# v3pow_1_4v7.net
KiCad netlist of a schematic drawn in EAGLE
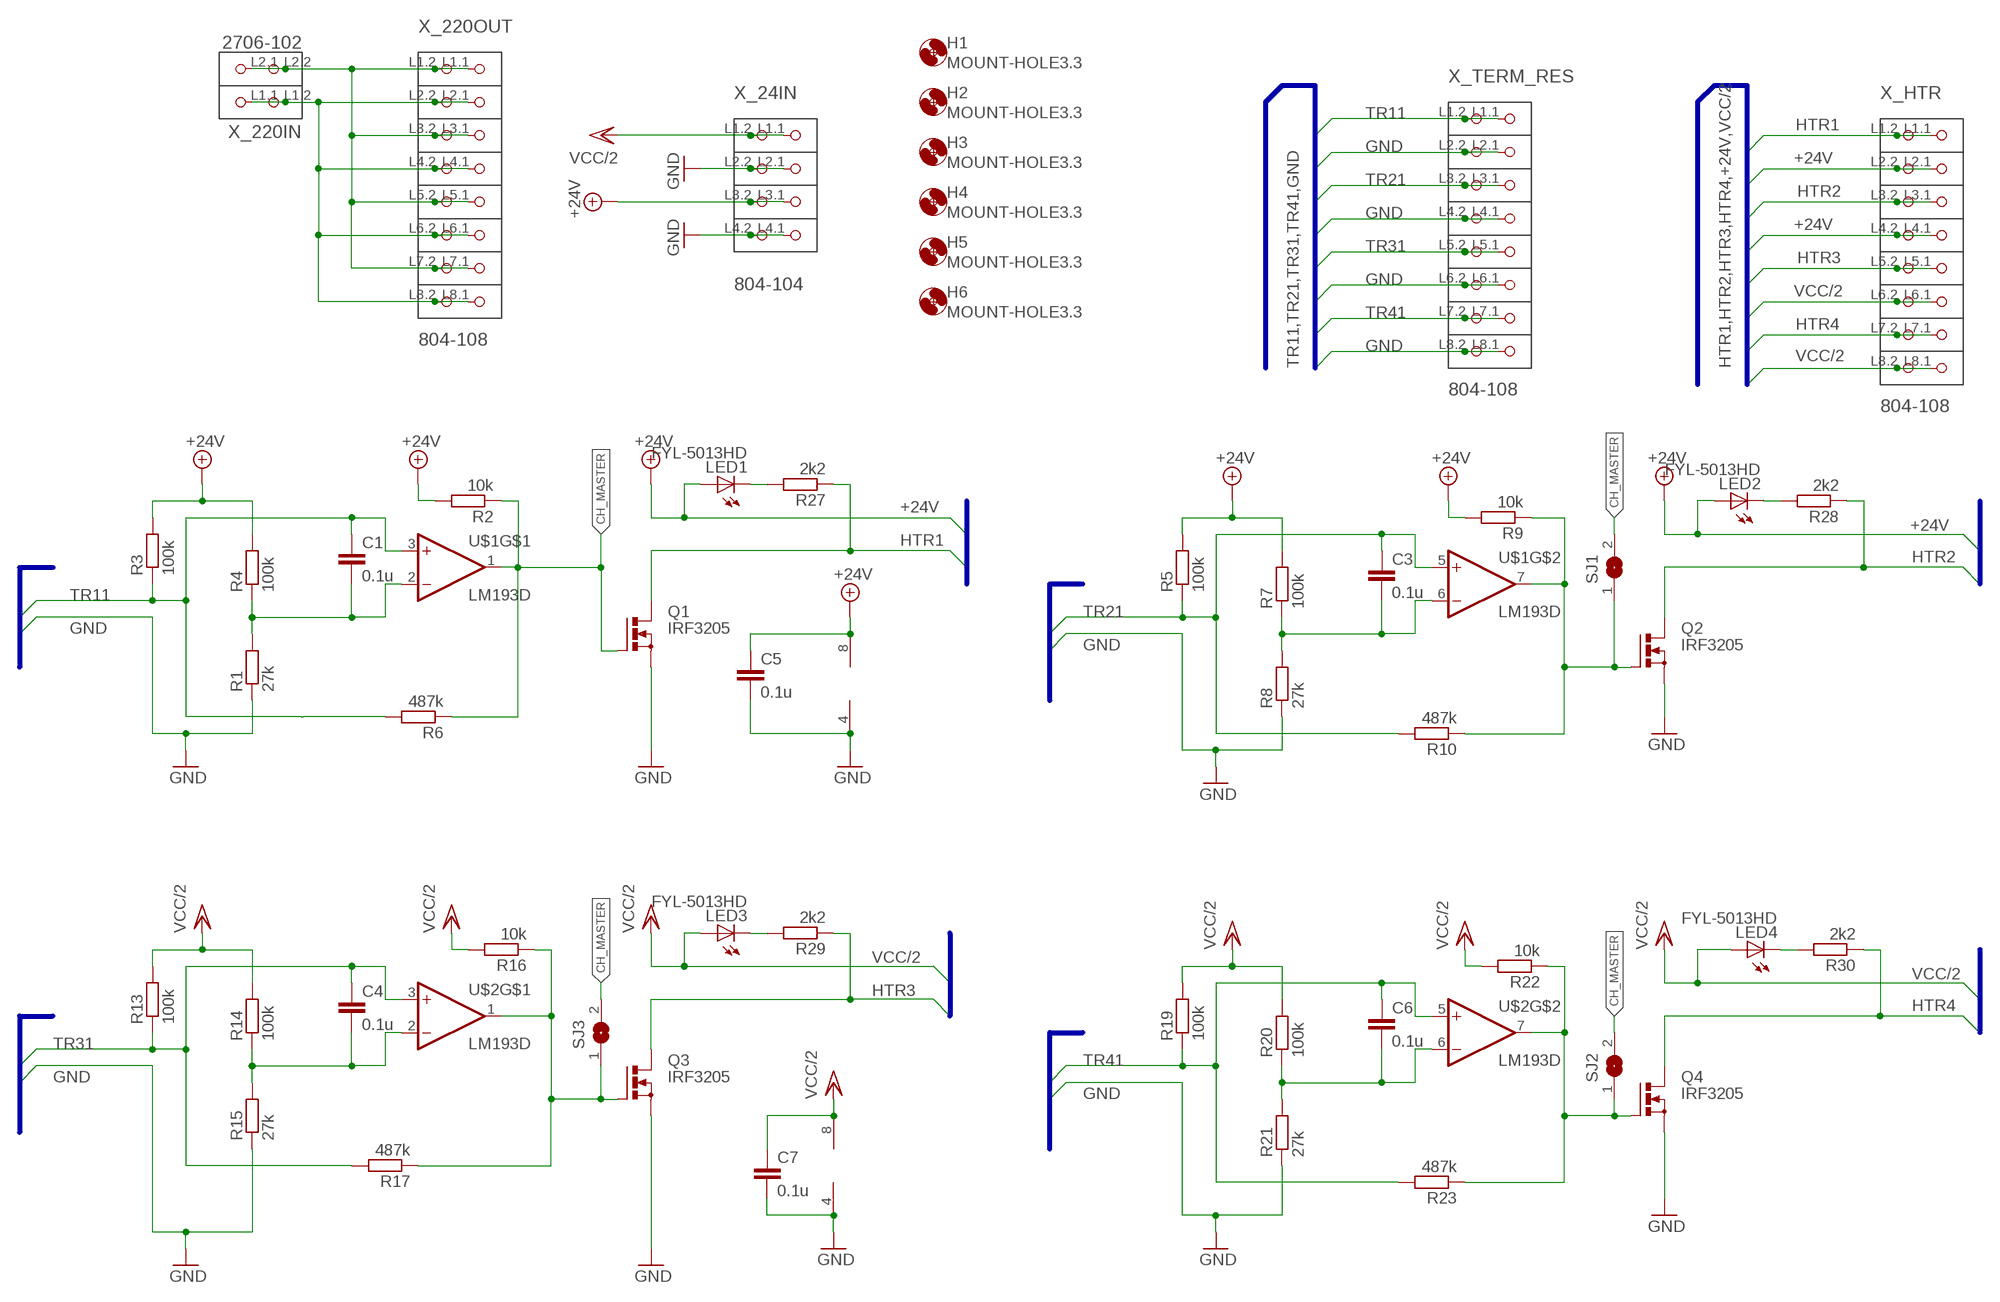
[diagram p0: schematic, sheet 1]

(export (version "E")
  (design (tool "Eeschema 10.0.6"))
  (components
    (comp (ref "C1")
      (value "0.1u")
      (footprint "eagle-import:C0805")
      (libsource (lib "eagle-import") (part "C-EUC0805"))
    )
    (comp (ref "C3")
      (value "0.1u")
      (footprint "eagle-import:C0805")
      (libsource (lib "eagle-import") (part "C-EUC0805"))
    )
    (comp (ref "C4")
      (value "0.1u")
      (footprint "eagle-import:C0805")
      (libsource (lib "eagle-import") (part "C-EUC0805"))
    )
    (comp (ref "C5")
      (value "0.1u")
      (footprint "eagle-import:C0805")
      (libsource (lib "eagle-import") (part "C-EUC0805"))
    )
    (comp (ref "C6")
      (value "0.1u")
      (footprint "eagle-import:C0805")
      (libsource (lib "eagle-import") (part "C-EUC0805"))
    )
    (comp (ref "C7")
      (value "0.1u")
      (footprint "eagle-import:C0805")
      (libsource (lib "eagle-import") (part "C-EUC0805"))
    )
    (comp (ref "H1")
      (value "MOUNT-HOLE3.3")
      (footprint "eagle-import:3,3")
      (libsource (lib "eagle-import") (part "MOUNT-HOLE3.3"))
    )
    (comp (ref "H2")
      (value "MOUNT-HOLE3.3")
      (footprint "eagle-import:3,3")
      (libsource (lib "eagle-import") (part "MOUNT-HOLE3.3"))
    )
    (comp (ref "H3")
      (value "MOUNT-HOLE3.3")
      (footprint "eagle-import:3,3")
      (libsource (lib "eagle-import") (part "MOUNT-HOLE3.3"))
    )
    (comp (ref "H4")
      (value "MOUNT-HOLE3.3")
      (footprint "eagle-import:3,3")
      (libsource (lib "eagle-import") (part "MOUNT-HOLE3.3"))
    )
    (comp (ref "H5")
      (value "MOUNT-HOLE3.3")
      (footprint "eagle-import:3,3")
      (libsource (lib "eagle-import") (part "MOUNT-HOLE3.3"))
    )
    (comp (ref "H6")
      (value "MOUNT-HOLE3.3")
      (footprint "eagle-import:3,3")
      (libsource (lib "eagle-import") (part "MOUNT-HOLE3.3"))
    )
    (comp (ref "LED1")
      (value "FYL-5013HD")
      (footprint "eagle-import:LED5MM")
      (libsource (lib "eagle-import") (part "LED5MM"))
    )
    (comp (ref "LED2")
      (value "FYL-5013HD")
      (footprint "eagle-import:LED5MM")
      (libsource (lib "eagle-import") (part "LED5MM"))
    )
    (comp (ref "LED3")
      (value "FYL-5013HD")
      (footprint "eagle-import:LED5MM")
      (libsource (lib "eagle-import") (part "LED5MM"))
    )
    (comp (ref "LED4")
      (value "FYL-5013HD")
      (footprint "eagle-import:LED5MM")
      (libsource (lib "eagle-import") (part "LED5MM"))
    )
    (comp (ref "Q1")
      (value "IRF3205")
      (footprint "eagle-import:TO220BV")
      (libsource (lib "eagle-import") (part "PMOSFET_NTO220BV"))
    )
    (comp (ref "Q2")
      (value "IRF3205")
      (footprint "eagle-import:TO220BV")
      (libsource (lib "eagle-import") (part "PMOSFET_NTO220BV"))
    )
    (comp (ref "Q3")
      (value "IRF3205")
      (footprint "eagle-import:TO220BV")
      (libsource (lib "eagle-import") (part "PMOSFET_NTO220BV"))
    )
    (comp (ref "Q4")
      (value "IRF3205")
      (footprint "eagle-import:TO220BV")
      (libsource (lib "eagle-import") (part "PMOSFET_NTO220BV"))
    )
    (comp (ref "R1")
      (value "27k")
      (footprint "eagle-import:M0805")
      (libsource (lib "eagle-import") (part "R-EU_M0805"))
    )
    (comp (ref "R2")
      (value "10k")
      (footprint "eagle-import:M0805")
      (libsource (lib "eagle-import") (part "R-EU_M0805"))
    )
    (comp (ref "R3")
      (value "100k")
      (footprint "eagle-import:M0805")
      (libsource (lib "eagle-import") (part "R-EU_M0805"))
    )
    (comp (ref "R4")
      (value "100k")
      (footprint "eagle-import:M0805")
      (libsource (lib "eagle-import") (part "R-EU_M0805"))
    )
    (comp (ref "R5")
      (value "100k")
      (footprint "eagle-import:M0805")
      (libsource (lib "eagle-import") (part "R-EU_M0805"))
    )
    (comp (ref "R6")
      (value "487k")
      (footprint "eagle-import:M0805")
      (libsource (lib "eagle-import") (part "R-EU_M0805"))
    )
    (comp (ref "R7")
      (value "100k")
      (footprint "eagle-import:M0805")
      (libsource (lib "eagle-import") (part "R-EU_M0805"))
    )
    (comp (ref "R8")
      (value "27k")
      (footprint "eagle-import:M0805")
      (libsource (lib "eagle-import") (part "R-EU_M0805"))
    )
    (comp (ref "R9")
      (value "10k")
      (footprint "eagle-import:M0805")
      (libsource (lib "eagle-import") (part "R-EU_M0805"))
    )
    (comp (ref "R10")
      (value "487k")
      (footprint "eagle-import:M0805")
      (libsource (lib "eagle-import") (part "R-EU_M0805"))
    )
    (comp (ref "R13")
      (value "100k")
      (footprint "eagle-import:M0805")
      (libsource (lib "eagle-import") (part "R-EU_M0805"))
    )
    (comp (ref "R14")
      (value "100k")
      (footprint "eagle-import:M0805")
      (libsource (lib "eagle-import") (part "R-EU_M0805"))
    )
    (comp (ref "R15")
      (value "27k")
      (footprint "eagle-import:M0805")
      (libsource (lib "eagle-import") (part "R-EU_M0805"))
    )
    (comp (ref "R16")
      (value "10k")
      (footprint "eagle-import:M0805")
      (libsource (lib "eagle-import") (part "R-EU_M0805"))
    )
    (comp (ref "R17")
      (value "487k")
      (footprint "eagle-import:M0805")
      (libsource (lib "eagle-import") (part "R-EU_M0805"))
    )
    (comp (ref "R19")
      (value "100k")
      (footprint "eagle-import:M0805")
      (libsource (lib "eagle-import") (part "R-EU_M0805"))
    )
    (comp (ref "R20")
      (value "100k")
      (footprint "eagle-import:M0805")
      (libsource (lib "eagle-import") (part "R-EU_M0805"))
    )
    (comp (ref "R21")
      (value "27k")
      (footprint "eagle-import:M0805")
      (libsource (lib "eagle-import") (part "R-EU_M0805"))
    )
    (comp (ref "R22")
      (value "10k")
      (footprint "eagle-import:M0805")
      (libsource (lib "eagle-import") (part "R-EU_M0805"))
    )
    (comp (ref "R23")
      (value "487k")
      (footprint "eagle-import:M0805")
      (libsource (lib "eagle-import") (part "R-EU_M0805"))
    )
    (comp (ref "R27")
      (value "2k2")
      (footprint "eagle-import:M0805")
      (libsource (lib "eagle-import") (part "R-EU_M0805"))
    )
    (comp (ref "R28")
      (value "2k2")
      (footprint "eagle-import:M0805")
      (libsource (lib "eagle-import") (part "R-EU_M0805"))
    )
    (comp (ref "R29")
      (value "2k2")
      (footprint "eagle-import:M0805")
      (libsource (lib "eagle-import") (part "R-EU_M0805"))
    )
    (comp (ref "R30")
      (value "2k2")
      (footprint "eagle-import:M0805")
      (libsource (lib "eagle-import") (part "R-EU_M0805"))
    )
    (comp (ref "SJ1") (value "SJ") (footprint "eagle-import:SJ") (libsource (lib "eagle-import") (part "SJ")))
    (comp (ref "SJ2") (value "SJ") (footprint "eagle-import:SJ") (libsource (lib "eagle-import") (part "SJ")))
    (comp (ref "SJ3") (value "SJ") (footprint "eagle-import:SJ") (libsource (lib "eagle-import") (part "SJ")))
    (comp (ref "U$1")
      (value "LM193D")
      (footprint "eagle-import:SO08")
      (libsource (lib "eagle-import") (part "LM193D"))
    )
    (comp (ref "U$2")
      (value "LM193D")
      (footprint "eagle-import:SO08")
      (libsource (lib "eagle-import") (part "LM193D"))
    )
    (comp (ref "X_24IN")
      (value "804-104")
      (footprint "eagle-import:P-804-104")
      (libsource (lib "eagle-import") (part "804-104"))
    )
    (comp (ref "X_220IN")
      (value "2706-102")
      (footprint "eagle-import:P-2706-102")
      (libsource (lib "eagle-import") (part "2706-102"))
    )
    (comp (ref "X_220OUT")
      (value "804-108")
      (footprint "eagle-import:P-804-108")
      (libsource (lib "eagle-import") (part "804-108"))
    )
    (comp (ref "X_HTR")
      (value "804-108")
      (footprint "eagle-import:P-804-108")
      (libsource (lib "eagle-import") (part "804-108"))
    )
    (comp (ref "X_TERM_RES")
      (value "804-108")
      (footprint "eagle-import:P-804-108")
      (libsource (lib "eagle-import") (part "804-108"))
    )
  )
  (nets
    (net (code "5") (name "+24V") (class "Default")
      (node (ref "C5") (pin "1") (pinfunction "1_1") (pintype "passive"))
      (node (ref "LED1") (pin "A") (pinfunction "A_A") (pintype "passive"))
      (node (ref "LED2") (pin "A") (pinfunction "A_A") (pintype "passive"))
      (node (ref "R2") (pin "2") (pinfunction "2_2") (pintype "passive"))
      (node (ref "R3") (pin "2") (pinfunction "2_2") (pintype "passive"))
      (node (ref "R4") (pin "2") (pinfunction "2_2") (pintype "passive"))
      (node (ref "R5") (pin "2") (pinfunction "2_2") (pintype "passive"))
      (node (ref "R7") (pin "2") (pinfunction "2_2") (pintype "passive"))
      (node (ref "R9") (pin "2") (pinfunction "2_2") (pintype "passive"))
      (node (ref "U$1") (pin "8") (pinfunction "V+_8") (pintype "power_in"))
      (node (ref "X_24IN") (pin "L3.1") (pinfunction "P3.1_L3.1") (pintype "bidirectional"))
      (node (ref "X_24IN") (pin "L3.2") (pinfunction "P3.2_L3.2") (pintype "bidirectional"))
      (node (ref "X_HTR") (pin "L2.1") (pinfunction "P2.1_L2.1") (pintype "bidirectional"))
      (node (ref "X_HTR") (pin "L2.2") (pinfunction "P2.2_L2.2") (pintype "bidirectional"))
      (node (ref "X_HTR") (pin "L4.1") (pinfunction "P4.1_L4.1") (pintype "bidirectional"))
      (node (ref "X_HTR") (pin "L4.2") (pinfunction "P4.2_L4.2") (pintype "bidirectional"))
    )
    (net (code "6") (name "/HTR1") (class "Default")
      (node (ref "Q1") (pin "D") (pinfunction "D_D") (pintype "passive"))
      (node (ref "R27") (pin "1") (pinfunction "1_1") (pintype "passive"))
      (node (ref "X_HTR") (pin "L1.1") (pinfunction "P1.1_L1.1") (pintype "bidirectional"))
      (node (ref "X_HTR") (pin "L1.2") (pinfunction "P1.2_L1.2") (pintype "bidirectional"))
    )
    (net (code "7") (name "/HTR2") (class "Default")
      (node (ref "Q2") (pin "D") (pinfunction "D_D") (pintype "passive"))
      (node (ref "R28") (pin "1") (pinfunction "1_1") (pintype "passive"))
      (node (ref "X_HTR") (pin "L3.1") (pinfunction "P3.1_L3.1") (pintype "bidirectional"))
      (node (ref "X_HTR") (pin "L3.2") (pinfunction "P3.2_L3.2") (pintype "bidirectional"))
    )
    (net (code "8") (name "/HTR3") (class "Default")
      (node (ref "Q3") (pin "D") (pinfunction "D_D") (pintype "passive"))
      (node (ref "R29") (pin "1") (pinfunction "1_1") (pintype "passive"))
      (node (ref "X_HTR") (pin "L5.1") (pinfunction "P5.1_L5.1") (pintype "bidirectional"))
      (node (ref "X_HTR") (pin "L5.2") (pinfunction "P5.2_L5.2") (pintype "bidirectional"))
    )
    (net (code "9") (name "/HTR4") (class "Default")
      (node (ref "Q4") (pin "D") (pinfunction "D_D") (pintype "passive"))
      (node (ref "R30") (pin "1") (pinfunction "1_1") (pintype "passive"))
      (node (ref "X_HTR") (pin "L7.1") (pinfunction "P7.1_L7.1") (pintype "bidirectional"))
      (node (ref "X_HTR") (pin "L7.2") (pinfunction "P7.2_L7.2") (pintype "bidirectional"))
    )
    (net (code "10") (name "/TR11") (class "Default")
      (node (ref "C1") (pin "1") (pinfunction "1_1") (pintype "passive"))
      (node (ref "R3") (pin "1") (pinfunction "1_1") (pintype "passive"))
      (node (ref "R6") (pin "2") (pinfunction "2_2") (pintype "passive"))
      (node (ref "U$1") (pin "3") (pinfunction "+IN_3") (pintype "input"))
      (node (ref "X_TERM_RES") (pin "L1.1") (pinfunction "P1.1_L1.1") (pintype "bidirectional"))
      (node (ref "X_TERM_RES") (pin "L1.2") (pinfunction "P1.2_L1.2") (pintype "bidirectional"))
    )
    (net (code "11") (name "/TR21") (class "Default")
      (node (ref "C3") (pin "1") (pinfunction "1_1") (pintype "passive"))
      (node (ref "R10") (pin "2") (pinfunction "2_2") (pintype "passive"))
      (node (ref "R5") (pin "1") (pinfunction "1_1") (pintype "passive"))
      (node (ref "U$1") (pin "5") (pinfunction "+IN_5") (pintype "input"))
      (node (ref "X_TERM_RES") (pin "L3.1") (pinfunction "P3.1_L3.1") (pintype "bidirectional"))
      (node (ref "X_TERM_RES") (pin "L3.2") (pinfunction "P3.2_L3.2") (pintype "bidirectional"))
    )
    (net (code "12") (name "/TR31") (class "Default")
      (node (ref "C4") (pin "1") (pinfunction "1_1") (pintype "passive"))
      (node (ref "R13") (pin "1") (pinfunction "1_1") (pintype "passive"))
      (node (ref "R17") (pin "2") (pinfunction "2_2") (pintype "passive"))
      (node (ref "U$2") (pin "3") (pinfunction "+IN_3") (pintype "input"))
      (node (ref "X_TERM_RES") (pin "L5.1") (pinfunction "P5.1_L5.1") (pintype "bidirectional"))
      (node (ref "X_TERM_RES") (pin "L5.2") (pinfunction "P5.2_L5.2") (pintype "bidirectional"))
    )
    (net (code "13") (name "/TR41") (class "Default")
      (node (ref "C6") (pin "1") (pinfunction "1_1") (pintype "passive"))
      (node (ref "R19") (pin "1") (pinfunction "1_1") (pintype "passive"))
      (node (ref "R23") (pin "2") (pinfunction "2_2") (pintype "passive"))
      (node (ref "U$2") (pin "5") (pinfunction "+IN_5") (pintype "input"))
      (node (ref "X_TERM_RES") (pin "L7.1") (pinfunction "P7.1_L7.1") (pintype "bidirectional"))
      (node (ref "X_TERM_RES") (pin "L7.2") (pinfunction "P7.2_L7.2") (pintype "bidirectional"))
    )
    (net (code "17") (name "CH_MASTER") (class "Default")
      (node (ref "Q1") (pin "G") (pinfunction "G_G") (pintype "passive"))
      (node (ref "R2") (pin "1") (pinfunction "1_1") (pintype "passive"))
      (node (ref "R6") (pin "1") (pinfunction "1_1") (pintype "passive"))
      (node (ref "SJ1") (pin "2") (pinfunction "2_2") (pintype "passive"))
      (node (ref "SJ2") (pin "2") (pinfunction "2_2") (pintype "passive"))
      (node (ref "SJ3") (pin "2") (pinfunction "2_2") (pintype "passive"))
      (node (ref "U$1") (pin "1") (pinfunction "OUT_1") (pintype "output"))
    )
    (net (code "18") (name "GND") (class "Default")
      (node (ref "C5") (pin "2") (pinfunction "2_2") (pintype "passive"))
      (node (ref "C7") (pin "2") (pinfunction "2_2") (pintype "passive"))
      (node (ref "Q1") (pin "S") (pinfunction "S_S") (pintype "passive"))
      (node (ref "Q2") (pin "S") (pinfunction "S_S") (pintype "passive"))
      (node (ref "Q3") (pin "S") (pinfunction "S_S") (pintype "passive"))
      (node (ref "Q4") (pin "S") (pinfunction "S_S") (pintype "passive"))
      (node (ref "R1") (pin "1") (pinfunction "1_1") (pintype "passive"))
      (node (ref "R15") (pin "1") (pinfunction "1_1") (pintype "passive"))
      (node (ref "R21") (pin "1") (pinfunction "1_1") (pintype "passive"))
      (node (ref "R8") (pin "1") (pinfunction "1_1") (pintype "passive"))
      (node (ref "U$1") (pin "4") (pinfunction "V-_4") (pintype "power_in"))
      (node (ref "U$2") (pin "4") (pinfunction "V-_4") (pintype "power_in"))
      (node (ref "X_24IN") (pin "L2.1") (pinfunction "P2.1_L2.1") (pintype "bidirectional"))
      (node (ref "X_24IN") (pin "L2.2") (pinfunction "P2.2_L2.2") (pintype "bidirectional"))
      (node (ref "X_24IN") (pin "L4.1") (pinfunction "P4.1_L4.1") (pintype "bidirectional"))
      (node (ref "X_24IN") (pin "L4.2") (pinfunction "P4.2_L4.2") (pintype "bidirectional"))
      (node (ref "X_TERM_RES") (pin "L2.1") (pinfunction "P2.1_L2.1") (pintype "bidirectional"))
      (node (ref "X_TERM_RES") (pin "L2.2") (pinfunction "P2.2_L2.2") (pintype "bidirectional"))
      (node (ref "X_TERM_RES") (pin "L4.1") (pinfunction "P4.1_L4.1") (pintype "bidirectional"))
      (node (ref "X_TERM_RES") (pin "L4.2") (pinfunction "P4.2_L4.2") (pintype "bidirectional"))
      (node (ref "X_TERM_RES") (pin "L6.1") (pinfunction "P6.1_L6.1") (pintype "bidirectional"))
      (node (ref "X_TERM_RES") (pin "L6.2") (pinfunction "P6.2_L6.2") (pintype "bidirectional"))
      (node (ref "X_TERM_RES") (pin "L8.1") (pinfunction "P8.1_L8.1") (pintype "bidirectional"))
      (node (ref "X_TERM_RES") (pin "L8.2") (pinfunction "P8.2_L8.2") (pintype "bidirectional"))
    )
    (net (code "19") (name "Net-(LED1-C)") (class "Default")
      (node (ref "LED1") (pin "K") (pinfunction "C_K") (pintype "passive"))
      (node (ref "R27") (pin "2") (pinfunction "2_2") (pintype "passive"))
    )
    (net (code "20") (name "Net-(LED2-C)") (class "Default")
      (node (ref "LED2") (pin "K") (pinfunction "C_K") (pintype "passive"))
      (node (ref "R28") (pin "2") (pinfunction "2_2") (pintype "passive"))
    )
    (net (code "21") (name "Net-(LED3-C)") (class "Default")
      (node (ref "LED3") (pin "K") (pinfunction "C_K") (pintype "passive"))
      (node (ref "R29") (pin "2") (pinfunction "2_2") (pintype "passive"))
    )
    (net (code "22") (name "Net-(LED4-C)") (class "Default")
      (node (ref "LED4") (pin "K") (pinfunction "C_K") (pintype "passive"))
      (node (ref "R30") (pin "2") (pinfunction "2_2") (pintype "passive"))
    )
    (net (code "23") (name "Net-(U$1A--IN)") (class "Default")
      (node (ref "C1") (pin "2") (pinfunction "2_2") (pintype "passive"))
      (node (ref "R1") (pin "2") (pinfunction "2_2") (pintype "passive"))
      (node (ref "R4") (pin "1") (pinfunction "1_1") (pintype "passive"))
      (node (ref "U$1") (pin "2") (pinfunction "-IN_2") (pintype "input"))
    )
    (net (code "24") (name "Net-(U$1B--IN)") (class "Default")
      (node (ref "C3") (pin "2") (pinfunction "2_2") (pintype "passive"))
      (node (ref "R7") (pin "1") (pinfunction "1_1") (pintype "passive"))
      (node (ref "R8") (pin "2") (pinfunction "2_2") (pintype "passive"))
      (node (ref "U$1") (pin "6") (pinfunction "-IN_6") (pintype "input"))
    )
    (net (code "25") (name "Net-(U$1B-OUT)") (class "Default")
      (node (ref "Q2") (pin "G") (pinfunction "G_G") (pintype "passive"))
      (node (ref "R10") (pin "1") (pinfunction "1_1") (pintype "passive"))
      (node (ref "R9") (pin "1") (pinfunction "1_1") (pintype "passive"))
      (node (ref "SJ1") (pin "1") (pinfunction "1_1") (pintype "passive"))
      (node (ref "U$1") (pin "7") (pinfunction "OUT_7") (pintype "output"))
    )
    (net (code "26") (name "Net-(U$2A--IN)") (class "Default")
      (node (ref "C4") (pin "2") (pinfunction "2_2") (pintype "passive"))
      (node (ref "R14") (pin "1") (pinfunction "1_1") (pintype "passive"))
      (node (ref "R15") (pin "2") (pinfunction "2_2") (pintype "passive"))
      (node (ref "U$2") (pin "2") (pinfunction "-IN_2") (pintype "input"))
    )
    (net (code "27") (name "Net-(U$2A-OUT)") (class "Default")
      (node (ref "Q3") (pin "G") (pinfunction "G_G") (pintype "passive"))
      (node (ref "R16") (pin "1") (pinfunction "1_1") (pintype "passive"))
      (node (ref "R17") (pin "1") (pinfunction "1_1") (pintype "passive"))
      (node (ref "SJ3") (pin "1") (pinfunction "1_1") (pintype "passive"))
      (node (ref "U$2") (pin "1") (pinfunction "OUT_1") (pintype "output"))
    )
    (net (code "28") (name "Net-(U$2B--IN)") (class "Default")
      (node (ref "C6") (pin "2") (pinfunction "2_2") (pintype "passive"))
      (node (ref "R20") (pin "1") (pinfunction "1_1") (pintype "passive"))
      (node (ref "R21") (pin "2") (pinfunction "2_2") (pintype "passive"))
      (node (ref "U$2") (pin "6") (pinfunction "-IN_6") (pintype "input"))
    )
    (net (code "29") (name "Net-(U$2B-OUT)") (class "Default")
      (node (ref "Q4") (pin "G") (pinfunction "G_G") (pintype "passive"))
      (node (ref "R22") (pin "1") (pinfunction "1_1") (pintype "passive"))
      (node (ref "R23") (pin "1") (pinfunction "1_1") (pintype "passive"))
      (node (ref "SJ2") (pin "1") (pinfunction "1_1") (pintype "passive"))
      (node (ref "U$2") (pin "7") (pinfunction "OUT_7") (pintype "output"))
    )
    (net (code "30") (name "Net-(X_220IN-P1.1)") (class "Default")
      (node (ref "X_220IN") (pin "L1.1") (pinfunction "P1.1_L1.1") (pintype "bidirectional"))
      (node (ref "X_220IN") (pin "L1.2") (pinfunction "P1.2_L1.2") (pintype "bidirectional"))
      (node (ref "X_220OUT") (pin "L2.1") (pinfunction "P2.1_L2.1") (pintype "bidirectional"))
      (node (ref "X_220OUT") (pin "L2.2") (pinfunction "P2.2_L2.2") (pintype "bidirectional"))
      (node (ref "X_220OUT") (pin "L4.1") (pinfunction "P4.1_L4.1") (pintype "bidirectional"))
      (node (ref "X_220OUT") (pin "L4.2") (pinfunction "P4.2_L4.2") (pintype "bidirectional"))
      (node (ref "X_220OUT") (pin "L6.1") (pinfunction "P6.1_L6.1") (pintype "bidirectional"))
      (node (ref "X_220OUT") (pin "L6.2") (pinfunction "P6.2_L6.2") (pintype "bidirectional"))
      (node (ref "X_220OUT") (pin "L8.1") (pinfunction "P8.1_L8.1") (pintype "bidirectional"))
      (node (ref "X_220OUT") (pin "L8.2") (pinfunction "P8.2_L8.2") (pintype "bidirectional"))
    )
    (net (code "31") (name "Net-(X_220IN-P2.1)") (class "Default")
      (node (ref "X_220IN") (pin "L2.1") (pinfunction "P2.1_L2.1") (pintype "bidirectional"))
      (node (ref "X_220IN") (pin "L2.2") (pinfunction "P2.2_L2.2") (pintype "bidirectional"))
      (node (ref "X_220OUT") (pin "L1.1") (pinfunction "P1.1_L1.1") (pintype "bidirectional"))
      (node (ref "X_220OUT") (pin "L1.2") (pinfunction "P1.2_L1.2") (pintype "bidirectional"))
      (node (ref "X_220OUT") (pin "L3.1") (pinfunction "P3.1_L3.1") (pintype "bidirectional"))
      (node (ref "X_220OUT") (pin "L3.2") (pinfunction "P3.2_L3.2") (pintype "bidirectional"))
      (node (ref "X_220OUT") (pin "L5.1") (pinfunction "P5.1_L5.1") (pintype "bidirectional"))
      (node (ref "X_220OUT") (pin "L5.2") (pinfunction "P5.2_L5.2") (pintype "bidirectional"))
      (node (ref "X_220OUT") (pin "L7.1") (pinfunction "P7.1_L7.1") (pintype "bidirectional"))
      (node (ref "X_220OUT") (pin "L7.2") (pinfunction "P7.2_L7.2") (pintype "bidirectional"))
    )
    (net (code "32") (name "VCC{slash}2") (class "Default")
      (node (ref "C7") (pin "1") (pinfunction "1_1") (pintype "passive"))
      (node (ref "LED3") (pin "A") (pinfunction "A_A") (pintype "passive"))
      (node (ref "LED4") (pin "A") (pinfunction "A_A") (pintype "passive"))
      (node (ref "R13") (pin "2") (pinfunction "2_2") (pintype "passive"))
      (node (ref "R14") (pin "2") (pinfunction "2_2") (pintype "passive"))
      (node (ref "R16") (pin "2") (pinfunction "2_2") (pintype "passive"))
      (node (ref "R19") (pin "2") (pinfunction "2_2") (pintype "passive"))
      (node (ref "R20") (pin "2") (pinfunction "2_2") (pintype "passive"))
      (node (ref "R22") (pin "2") (pinfunction "2_2") (pintype "passive"))
      (node (ref "U$2") (pin "8") (pinfunction "V+_8") (pintype "power_in"))
      (node (ref "X_24IN") (pin "L1.1") (pinfunction "P1.1_L1.1") (pintype "bidirectional"))
      (node (ref "X_24IN") (pin "L1.2") (pinfunction "P1.2_L1.2") (pintype "bidirectional"))
      (node (ref "X_HTR") (pin "L6.1") (pinfunction "P6.1_L6.1") (pintype "bidirectional"))
      (node (ref "X_HTR") (pin "L6.2") (pinfunction "P6.2_L6.2") (pintype "bidirectional"))
      (node (ref "X_HTR") (pin "L8.1") (pinfunction "P8.1_L8.1") (pintype "bidirectional"))
      (node (ref "X_HTR") (pin "L8.2") (pinfunction "P8.2_L8.2") (pintype "bidirectional"))
    )
  )
)
